# LCD_Dev_SCH_0.net
KiCad netlist of a schematic drawn in Altium Designer
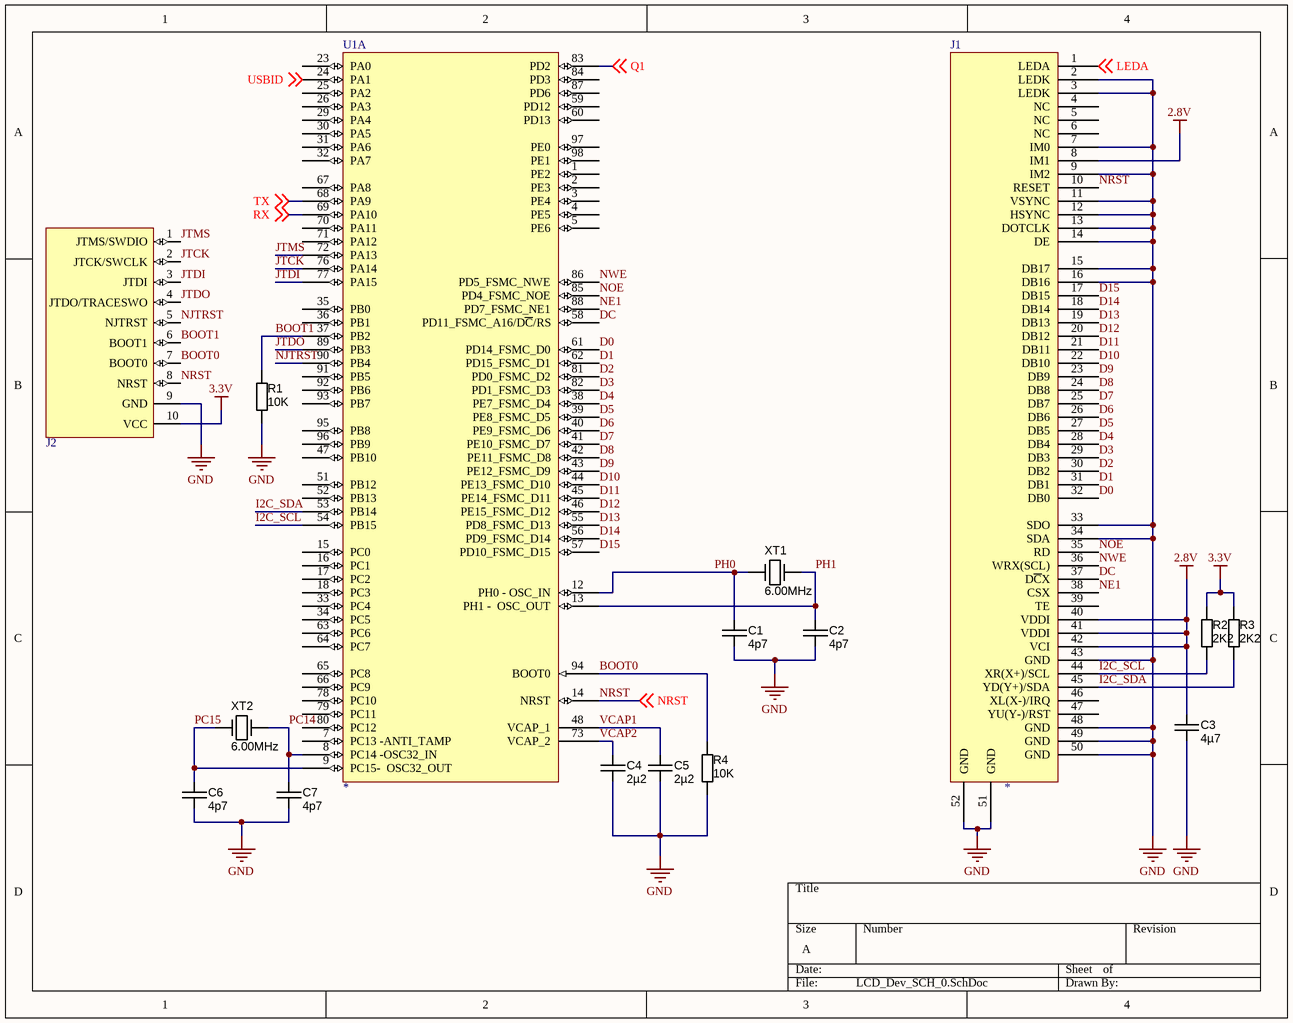
[diagram p0: LCD_Dev_SCH_0.SchDoc]

(export (version "E")
  (design (tool "Eeschema 10.0.6"))
  (components
    (comp (ref "C1")
      (value "4p7")
      (footprint "CAPC1608X90N")
      (description "Capacitor SMD Cer 4.7pF ±0.25pF 100V NP0 0603")
      (fields (field (name "TOLERANCE") "±0.25pF") (field (name "Comment") "approved sub OK"))
      (libsource (lib "PBL - Capacitors") (part "CAPC_4p7_100V_0603"))
    )
    (comp (ref "C2")
      (value "4p7")
      (footprint "CAPC1608X90N")
      (description "Capacitor SMD Cer 4.7pF ±0.25pF 100V NP0 0603")
      (fields (field (name "TOLERANCE") "±0.25pF") (field (name "Comment") "approved sub OK"))
      (libsource (lib "PBL - Capacitors") (part "CAPC_4p7_100V_0603"))
    )
    (comp (ref "C3")
      (value "4µ7")
      (footprint "CAPC2012X135N")
      (description "Capacitor SMD Cer 4.7uF 10% 16V X5R 0805")
      (fields (field (name "TOLERANCE") "±10%") (field (name "Comment") "approved sub OK"))
      (libsource (lib "PBL - Capacitors") (part "CAPC_4u7_0805"))
    )
    (comp (ref "C4")
      (value "2µ2")
      (footprint "CAPC2012X135N")
      (description "Capacitor SMD Cer 2.2uF 10% 16V X7R 0805")
      (fields (field (name "TOLERANCE") "±10%") (field (name "Comment") "approved sub OK"))
      (libsource (lib "PBL - Capacitors") (part "CAPC_2u2_0805"))
    )
    (comp (ref "C5")
      (value "2µ2")
      (footprint "CAPC2012X135N")
      (description "Capacitor SMD Cer 2.2uF 10% 16V X7R 0805")
      (fields (field (name "TOLERANCE") "±10%") (field (name "Comment") "approved sub OK"))
      (libsource (lib "PBL - Capacitors") (part "CAPC_2u2_0805"))
    )
    (comp (ref "C6")
      (value "4p7")
      (footprint "CAPC1608X90N")
      (description "Capacitor SMD Cer 4.7pF ±0.25pF 100V NP0 0603")
      (fields (field (name "TOLERANCE") "±0.25pF") (field (name "Comment") "approved sub OK"))
      (libsource (lib "PBL - Capacitors") (part "CAPC_4p7_100V_0603"))
    )
    (comp (ref "C7")
      (value "4p7")
      (footprint "CAPC1608X90N")
      (description "Capacitor SMD Cer 4.7pF ±0.25pF 100V NP0 0603")
      (fields (field (name "TOLERANCE") "±0.25pF") (field (name "Comment") "approved sub OK"))
      (libsource (lib "PBL - Capacitors") (part "CAPC_4p7_100V_0603"))
    )
    (comp (ref "J1")
      (value "*")
      (footprint "ER-CON50HT-1")
      (description "3.5”TFT LCD Display Port (i80/6800/FSMC etc)")
      (libsource (lib "co2_meter_integrated_library") (part "LCD-Port"))
    )
    (comp (ref "J2")
      (value "*")
      (footprint "SWJ-DP connector")
      (description "10 pin Serial Wire JTAG Debug Port")
      (libsource (lib "co2_meter_integrated_library") (part "SWJ-Debug Port"))
    )
    (comp (ref "R1")
      (value "10K")
      (footprint "RESC1608X55N")
      (description "Resistor SMD chip 10k Ohm 0.1W 5% 0603")
      (fields (field (name "TOLERANCE") "±5%") (field (name "Comment") "Thick Film"))
      (libsource (lib "PBL - Resistors") (part "RES_10K_0603_5%"))
    )
    (comp (ref "R2")
      (value "2K2")
      (footprint "RESC1608X55N")
      (description "Resistor SMD chip 2.2k Ohm 0.1W 5% 0603")
      (fields (field (name "TOLERANCE") "±5%") (field (name "Comment") "Thick Film"))
      (libsource (lib "PBL - Resistors") (part "RES_2K2_0603_5%"))
    )
    (comp (ref "R3")
      (value "2K2")
      (footprint "RESC1608X55N")
      (description "Resistor SMD chip 2.2k Ohm 0.1W 5% 0603")
      (fields (field (name "TOLERANCE") "±5%") (field (name "Comment") "Thick Film"))
      (libsource (lib "PBL - Resistors") (part "RES_2K2_0603_5%"))
    )
    (comp (ref "R4")
      (value "10K")
      (footprint "RESC1608X55N")
      (description "Resistor SMD chip 10k Ohm 0.1W 5% 0603")
      (fields (field (name "TOLERANCE") "±5%") (field (name "Comment") "Thick Film"))
      (libsource (lib "PBL - Resistors") (part "RES_10K_0603_5%"))
    )
    (comp (ref "U1")
      (value "*")
      (footprint "LQFP100_STM32F4")
      (description "STM32F413VHT symbol for FSMC application with designated FSMC relevant pins")
      (libsource (lib "co2_meter_integrated_library") (part "STM32F413xH"))
    )
    (comp (ref "XT1")
      (value "6.00MHz")
      (footprint "CRYSTAL_HC49-US-SM")
      (description "Resonator Ceramic 6.00 MHz 30ppm")
      (libsource (lib "PBL - Resonators") (part "Crystal_6MHz_HC49/US"))
    )
    (comp (ref "XT2")
      (value "6.00MHz")
      (footprint "CRYSTAL_HC49-US-SM")
      (description "Resonator Ceramic 6.00 MHz 30ppm")
      (libsource (lib "PBL - Resonators") (part "Crystal_6MHz_HC49/US"))
    )
  )
  (nets
    (net (code "1") (name "/BOOT0") (class "Default")
      (node (ref "J2") (pin "7") (pinfunction "BOOT0_7") (pintype "bidirectional"))
      (node (ref "R4") (pin "1") (pinfunction "1_1") (pintype "passive"))
      (node (ref "U1") (pin "94") (pinfunction "BOOT0_94") (pintype "input"))
    )
    (net (code "2") (name "/BOOT1") (class "Default")
      (node (ref "J2") (pin "6") (pinfunction "BOOT1_6") (pintype "bidirectional"))
      (node (ref "R1") (pin "1") (pinfunction "1_1") (pintype "passive"))
      (node (ref "U1") (pin "37") (pinfunction "PB2_37") (pintype "bidirectional"))
    )
    (net (code "3") (name "/D0") (class "Default")
      (node (ref "J1") (pin "32") (pinfunction "DB0_32") (pintype "passive"))
      (node (ref "U1") (pin "61") (pinfunction "PD14_FSMC_D0_61") (pintype "bidirectional"))
    )
    (net (code "4") (name "/D1") (class "Default")
      (node (ref "J1") (pin "31") (pinfunction "DB1_31") (pintype "passive"))
      (node (ref "U1") (pin "62") (pinfunction "PD15_FSMC_D1_62") (pintype "bidirectional"))
    )
    (net (code "5") (name "/D2") (class "Default")
      (node (ref "J1") (pin "30") (pinfunction "DB2_30") (pintype "passive"))
      (node (ref "U1") (pin "81") (pinfunction "PD0_FSMC_D2_81") (pintype "bidirectional"))
    )
    (net (code "6") (name "/D3") (class "Default")
      (node (ref "J1") (pin "29") (pinfunction "DB3_29") (pintype "passive"))
      (node (ref "U1") (pin "82") (pinfunction "PD1_FSMC_D3_82") (pintype "bidirectional"))
    )
    (net (code "7") (name "/D4") (class "Default")
      (node (ref "J1") (pin "28") (pinfunction "DB4_28") (pintype "passive"))
      (node (ref "U1") (pin "38") (pinfunction "PE7_FSMC_D4_38") (pintype "bidirectional"))
    )
    (net (code "8") (name "/D5") (class "Default")
      (node (ref "J1") (pin "27") (pinfunction "DB5_27") (pintype "passive"))
      (node (ref "U1") (pin "39") (pinfunction "PE8_FSMC_D5_39") (pintype "bidirectional"))
    )
    (net (code "9") (name "/D6") (class "Default")
      (node (ref "J1") (pin "26") (pinfunction "DB6_26") (pintype "passive"))
      (node (ref "U1") (pin "40") (pinfunction "PE9_FSMC_D6_40") (pintype "bidirectional"))
    )
    (net (code "10") (name "/D7") (class "Default")
      (node (ref "J1") (pin "25") (pinfunction "DB7_25") (pintype "passive"))
      (node (ref "U1") (pin "41") (pinfunction "PE10_FSMC_D7_41") (pintype "bidirectional"))
    )
    (net (code "11") (name "/D8") (class "Default")
      (node (ref "J1") (pin "24") (pinfunction "DB8_24") (pintype "passive"))
      (node (ref "U1") (pin "42") (pinfunction "PE11_FSMC_D8_42") (pintype "bidirectional"))
    )
    (net (code "12") (name "/D9") (class "Default")
      (node (ref "J1") (pin "23") (pinfunction "DB9_23") (pintype "passive"))
      (node (ref "U1") (pin "43") (pinfunction "PE12_FSMC_D9_43") (pintype "bidirectional"))
    )
    (net (code "13") (name "/D10") (class "Default")
      (node (ref "J1") (pin "22") (pinfunction "DB10_22") (pintype "passive"))
      (node (ref "U1") (pin "44") (pinfunction "PE13_FSMC_D10_44") (pintype "bidirectional"))
    )
    (net (code "14") (name "/D11") (class "Default")
      (node (ref "J1") (pin "21") (pinfunction "DB11_21") (pintype "passive"))
      (node (ref "U1") (pin "45") (pinfunction "PE14_FSMC_D11_45") (pintype "bidirectional"))
    )
    (net (code "15") (name "/D12") (class "Default")
      (node (ref "J1") (pin "20") (pinfunction "DB12_20") (pintype "passive"))
      (node (ref "U1") (pin "46") (pinfunction "PE15_FSMC_D12_46") (pintype "bidirectional"))
    )
    (net (code "16") (name "/D13") (class "Default")
      (node (ref "J1") (pin "19") (pinfunction "DB13_19") (pintype "passive"))
      (node (ref "U1") (pin "55") (pinfunction "PD8_FSMC_D13_55") (pintype "bidirectional"))
    )
    (net (code "17") (name "/D14") (class "Default")
      (node (ref "J1") (pin "18") (pinfunction "DB14_18") (pintype "passive"))
      (node (ref "U1") (pin "56") (pinfunction "PD9_FSMC_D14_56") (pintype "bidirectional"))
    )
    (net (code "18") (name "/D15") (class "Default")
      (node (ref "J1") (pin "17") (pinfunction "DB15_17") (pintype "passive"))
      (node (ref "U1") (pin "57") (pinfunction "PD10_FSMC_D15_57") (pintype "bidirectional"))
    )
    (net (code "19") (name "/DC") (class "Default")
      (node (ref "J1") (pin "37") (pinfunction "D~{C}X_37") (pintype "passive"))
      (node (ref "U1") (pin "58") (pinfunction "PD11_FSMC_A16/D~{C}/RS_58") (pintype "bidirectional"))
    )
    (net (code "20") (name "/I2C_SCL") (class "Default")
      (node (ref "J1") (pin "44") (pinfunction "XR(X+)/SCL_44") (pintype "passive"))
      (node (ref "R2") (pin "2") (pinfunction "2_2") (pintype "passive"))
      (node (ref "U1") (pin "54") (pinfunction "PB15_54") (pintype "bidirectional"))
    )
    (net (code "21") (name "/I2C_SDA") (class "Default")
      (node (ref "J1") (pin "45") (pinfunction "YD(Y+)/SDA_45") (pintype "passive"))
      (node (ref "R3") (pin "2") (pinfunction "2_2") (pintype "passive"))
      (node (ref "U1") (pin "53") (pinfunction "PB14_53") (pintype "bidirectional"))
    )
    (net (code "22") (name "/JTCK") (class "Default")
      (node (ref "J2") (pin "2") (pinfunction "JTCK/SWCLK_2") (pintype "bidirectional"))
      (node (ref "U1") (pin "76") (pinfunction "PA14_76") (pintype "bidirectional"))
    )
    (net (code "23") (name "/JTDI") (class "Default")
      (node (ref "J2") (pin "3") (pinfunction "JTDI_3") (pintype "bidirectional"))
      (node (ref "U1") (pin "77") (pinfunction "PA15_77") (pintype "bidirectional"))
    )
    (net (code "24") (name "/JTDO") (class "Default")
      (node (ref "J2") (pin "4") (pinfunction "JTDO/TRACESWO_4") (pintype "bidirectional"))
      (node (ref "U1") (pin "89") (pinfunction "PB3_89") (pintype "bidirectional"))
    )
    (net (code "25") (name "/JTMS") (class "Default")
      (node (ref "J2") (pin "1") (pinfunction "JTMS/SWDIO_1") (pintype "bidirectional"))
      (node (ref "U1") (pin "72") (pinfunction "PA13_72") (pintype "bidirectional"))
    )
    (net (code "26") (name "/NE1") (class "Default")
      (node (ref "J1") (pin "38") (pinfunction "CSX_38") (pintype "passive"))
      (node (ref "U1") (pin "88") (pinfunction "PD7_FSMC_NE1_88") (pintype "bidirectional"))
    )
    (net (code "27") (name "/NJTRST") (class "Default")
      (node (ref "J2") (pin "5") (pinfunction "NJTRST_5") (pintype "bidirectional"))
      (node (ref "U1") (pin "90") (pinfunction "PB4_90") (pintype "bidirectional"))
    )
    (net (code "28") (name "/NOE") (class "Default")
      (node (ref "J1") (pin "35") (pinfunction "RD_35") (pintype "passive"))
      (node (ref "U1") (pin "85") (pinfunction "PD4_FSMC_NOE_85") (pintype "bidirectional"))
    )
    (net (code "29") (name "/NWE") (class "Default")
      (node (ref "J1") (pin "36") (pinfunction "WRX(SCL)_36") (pintype "passive"))
      (node (ref "U1") (pin "86") (pinfunction "PD5_FSMC_NWE_86") (pintype "bidirectional"))
    )
    (net (code "30") (name "/PC14") (class "Default")
      (node (ref "C7") (pin "1") (pintype "passive"))
      (node (ref "U1") (pin "8") (pinfunction "PC14_-OSC32_IN_8") (pintype "bidirectional"))
      (node (ref "XT2") (pin "2") (pinfunction "OUT_2") (pintype "passive"))
    )
    (net (code "31") (name "/PC15") (class "Default")
      (node (ref "C6") (pin "1") (pintype "passive"))
      (node (ref "U1") (pin "9") (pinfunction "PC15-__OSC32_OUT_9") (pintype "bidirectional"))
      (node (ref "XT2") (pin "1") (pinfunction "IN_1") (pintype "passive"))
    )
    (net (code "32") (name "/PH0") (class "Default")
      (node (ref "C1") (pin "1") (pintype "passive"))
      (node (ref "U1") (pin "12") (pinfunction "PH0_-_OSC_IN_12") (pintype "bidirectional"))
      (node (ref "XT1") (pin "1") (pinfunction "IN_1") (pintype "passive"))
    )
    (net (code "33") (name "/PH1") (class "Default")
      (node (ref "C2") (pin "1") (pintype "passive"))
      (node (ref "U1") (pin "13") (pinfunction "PH1_-__OSC_OUT_13") (pintype "bidirectional"))
      (node (ref "XT1") (pin "2") (pinfunction "OUT_2") (pintype "passive"))
    )
    (net (code "34") (name "/VCAP1") (class "Default")
      (node (ref "C5") (pin "1") (pintype "passive"))
      (node (ref "U1") (pin "48") (pinfunction "VCAP_1_48") (pintype "power_in"))
    )
    (net (code "35") (name "/VCAP2") (class "Default")
      (node (ref "C4") (pin "1") (pintype "passive"))
      (node (ref "U1") (pin "73") (pinfunction "VCAP_2_73") (pintype "power_in"))
    )
    (net (code "36") (name "2.8V") (class "Default")
      (node (ref "C3") (pin "1") (pintype "passive"))
      (node (ref "J1") (pin "40") (pinfunction "VDDI_40") (pintype "passive"))
      (node (ref "J1") (pin "41") (pinfunction "VDDI_41") (pintype "passive"))
      (node (ref "J1") (pin "42") (pinfunction "VCI_42") (pintype "passive"))
      (node (ref "J1") (pin "8") (pinfunction "IM1_8") (pintype "passive"))
    )
    (net (code "37") (name "3.3V") (class "Default")
      (node (ref "J2") (pin "10") (pinfunction "VCC_10") (pintype "power_in"))
      (node (ref "R2") (pin "1") (pinfunction "1_1") (pintype "passive"))
      (node (ref "R3") (pin "1") (pinfunction "1_1") (pintype "passive"))
    )
    (net (code "38") (name "GND") (class "Default")
      (node (ref "C1") (pin "2") (pintype "passive"))
      (node (ref "C2") (pin "2") (pintype "passive"))
      (node (ref "C3") (pin "2") (pintype "passive"))
      (node (ref "C4") (pin "2") (pintype "passive"))
      (node (ref "C5") (pin "2") (pintype "passive"))
      (node (ref "C6") (pin "2") (pintype "passive"))
      (node (ref "C7") (pin "2") (pintype "passive"))
      (node (ref "J1") (pin "11") (pinfunction "VSYNC_11") (pintype "passive"))
      (node (ref "J1") (pin "12") (pinfunction "HSYNC_12") (pintype "passive"))
      (node (ref "J1") (pin "13") (pinfunction "DOTCLK_13") (pintype "passive"))
      (node (ref "J1") (pin "14") (pinfunction "DE_14") (pintype "passive"))
      (node (ref "J1") (pin "15") (pinfunction "DB17_15") (pintype "passive"))
      (node (ref "J1") (pin "16") (pinfunction "DB16_16") (pintype "passive"))
      (node (ref "J1") (pin "2") (pinfunction "LEDK_2") (pintype "power_in"))
      (node (ref "J1") (pin "3") (pinfunction "LEDK_3") (pintype "power_in"))
      (node (ref "J1") (pin "33") (pinfunction "SDO_33") (pintype "passive"))
      (node (ref "J1") (pin "34") (pinfunction "SDA_34") (pintype "passive"))
      (node (ref "J1") (pin "43") (pinfunction "GND_43") (pintype "power_in"))
      (node (ref "J1") (pin "48") (pinfunction "GND_48") (pintype "power_in"))
      (node (ref "J1") (pin "49") (pinfunction "GND_49") (pintype "power_in"))
      (node (ref "J1") (pin "50") (pinfunction "GND_50") (pintype "power_in"))
      (node (ref "J1") (pin "51") (pinfunction "GND_51") (pintype "power_in"))
      (node (ref "J1") (pin "52") (pinfunction "GND_52") (pintype "power_in"))
      (node (ref "J1") (pin "7") (pinfunction "IM0_7") (pintype "passive"))
      (node (ref "J1") (pin "9") (pinfunction "IM2_9") (pintype "passive"))
      (node (ref "J2") (pin "9") (pinfunction "GND_9") (pintype "power_in"))
      (node (ref "R1") (pin "2") (pinfunction "2_2") (pintype "passive"))
      (node (ref "R4") (pin "2") (pinfunction "2_2") (pintype "passive"))
    )
    (net (code "39") (name "LEDA") (class "Default")
      (node (ref "J1") (pin "1") (pinfunction "LEDA_1") (pintype "power_in"))
    )
    (net (code "40") (name "NRST") (class "Default")
      (node (ref "J1") (pin "10") (pinfunction "RESET_10") (pintype "passive"))
      (node (ref "J2") (pin "8") (pinfunction "NRST_8") (pintype "bidirectional"))
      (node (ref "U1") (pin "14") (pinfunction "NRST_14") (pintype "bidirectional"))
    )
    (net (code "41") (name "Q1") (class "Default")
      (node (ref "U1") (pin "83") (pinfunction "PD2_83") (pintype "bidirectional"))
    )
    (net (code "42") (name "RX") (class "Default")
      (node (ref "U1") (pin "69") (pinfunction "PA10_69") (pintype "bidirectional"))
    )
    (net (code "43") (name "TX") (class "Default")
      (node (ref "U1") (pin "68") (pinfunction "PA9_68") (pintype "bidirectional"))
    )
    (net (code "44") (name "USBID") (class "Default")
      (node (ref "U1") (pin "24") (pinfunction "PA1_24") (pintype "bidirectional"))
    )
    (net (code "45") (name "unconnected-(J1-NC-Pad4)") (class "Default")
      (node (ref "J1") (pin "4") (pinfunction "NC_4") (pintype "passive"))
    )
    (net (code "46") (name "unconnected-(J1-NC-Pad5)") (class "Default")
      (node (ref "J1") (pin "5") (pinfunction "NC_5") (pintype "passive"))
    )
    (net (code "47") (name "unconnected-(J1-NC-Pad6)") (class "Default")
      (node (ref "J1") (pin "6") (pinfunction "NC_6") (pintype "passive"))
    )
    (net (code "48") (name "unconnected-(J1-TE-Pad39)") (class "Default")
      (node (ref "J1") (pin "39") (pinfunction "TE_39") (pintype "passive"))
    )
    (net (code "49") (name "unconnected-(J1-XL(X-){slash}IRQ-Pad46)") (class "Default")
      (node (ref "J1") (pin "46") (pinfunction "XL(X-)/IRQ_46") (pintype "passive"))
    )
    (net (code "50") (name "unconnected-(J1-YU(Y-){slash}RST-Pad47)") (class "Default")
      (node (ref "J1") (pin "47") (pinfunction "YU(Y-)/RST_47") (pintype "passive"))
    )
    (net (code "51") (name "unconnected-(U1A-PA0-Pad23)") (class "Default")
      (node (ref "U1") (pin "23") (pinfunction "PA0_23") (pintype "bidirectional"))
    )
    (net (code "52") (name "unconnected-(U1A-PA2-Pad25)") (class "Default")
      (node (ref "U1") (pin "25") (pinfunction "PA2_25") (pintype "bidirectional"))
    )
    (net (code "53") (name "unconnected-(U1A-PA3-Pad26)") (class "Default")
      (node (ref "U1") (pin "26") (pinfunction "PA3_26") (pintype "bidirectional"))
    )
    (net (code "54") (name "unconnected-(U1A-PA4-Pad29)") (class "Default")
      (node (ref "U1") (pin "29") (pinfunction "PA4_29") (pintype "bidirectional"))
    )
    (net (code "55") (name "unconnected-(U1A-PA5-Pad30)") (class "Default")
      (node (ref "U1") (pin "30") (pinfunction "PA5_30") (pintype "bidirectional"))
    )
    (net (code "56") (name "unconnected-(U1A-PA6-Pad31)") (class "Default")
      (node (ref "U1") (pin "31") (pinfunction "PA6_31") (pintype "bidirectional"))
    )
    (net (code "57") (name "unconnected-(U1A-PA7-Pad32)") (class "Default")
      (node (ref "U1") (pin "32") (pinfunction "PA7_32") (pintype "bidirectional"))
    )
    (net (code "58") (name "unconnected-(U1A-PA8-Pad67)") (class "Default")
      (node (ref "U1") (pin "67") (pinfunction "PA8_67") (pintype "bidirectional"))
    )
    (net (code "59") (name "unconnected-(U1A-PA11-Pad70)") (class "Default")
      (node (ref "U1") (pin "70") (pinfunction "PA11_70") (pintype "bidirectional"))
    )
    (net (code "60") (name "unconnected-(U1A-PA12-Pad71)") (class "Default")
      (node (ref "U1") (pin "71") (pinfunction "PA12_71") (pintype "bidirectional"))
    )
    (net (code "61") (name "unconnected-(U1A-PB0-Pad35)") (class "Default")
      (node (ref "U1") (pin "35") (pinfunction "PB0_35") (pintype "bidirectional"))
    )
    (net (code "62") (name "unconnected-(U1A-PB1-Pad36)") (class "Default")
      (node (ref "U1") (pin "36") (pinfunction "PB1_36") (pintype "bidirectional"))
    )
    (net (code "63") (name "unconnected-(U1A-PB5-Pad91)") (class "Default")
      (node (ref "U1") (pin "91") (pinfunction "PB5_91") (pintype "bidirectional"))
    )
    (net (code "64") (name "unconnected-(U1A-PB6-Pad92)") (class "Default")
      (node (ref "U1") (pin "92") (pinfunction "PB6_92") (pintype "bidirectional"))
    )
    (net (code "65") (name "unconnected-(U1A-PB7-Pad93)") (class "Default")
      (node (ref "U1") (pin "93") (pinfunction "PB7_93") (pintype "bidirectional"))
    )
    (net (code "66") (name "unconnected-(U1A-PB8-Pad95)") (class "Default")
      (node (ref "U1") (pin "95") (pinfunction "PB8_95") (pintype "bidirectional"))
    )
    (net (code "67") (name "unconnected-(U1A-PB9-Pad96)") (class "Default")
      (node (ref "U1") (pin "96") (pinfunction "PB9_96") (pintype "bidirectional"))
    )
    (net (code "68") (name "unconnected-(U1A-PB10-Pad47)") (class "Default")
      (node (ref "U1") (pin "47") (pinfunction "PB10_47") (pintype "bidirectional"))
    )
    (net (code "69") (name "unconnected-(U1A-PB12-Pad51)") (class "Default")
      (node (ref "U1") (pin "51") (pinfunction "PB12_51") (pintype "bidirectional"))
    )
    (net (code "70") (name "unconnected-(U1A-PB13-Pad52)") (class "Default")
      (node (ref "U1") (pin "52") (pinfunction "PB13_52") (pintype "bidirectional"))
    )
    (net (code "71") (name "unconnected-(U1A-PC0-Pad15)") (class "Default")
      (node (ref "U1") (pin "15") (pinfunction "PC0_15") (pintype "bidirectional"))
    )
    (net (code "72") (name "unconnected-(U1A-PC1-Pad16)") (class "Default")
      (node (ref "U1") (pin "16") (pinfunction "PC1_16") (pintype "bidirectional"))
    )
    (net (code "73") (name "unconnected-(U1A-PC2-Pad17)") (class "Default")
      (node (ref "U1") (pin "17") (pinfunction "PC2_17") (pintype "bidirectional"))
    )
    (net (code "74") (name "unconnected-(U1A-PC3-Pad18)") (class "Default")
      (node (ref "U1") (pin "18") (pinfunction "PC3_18") (pintype "bidirectional"))
    )
    (net (code "75") (name "unconnected-(U1A-PC4-Pad33)") (class "Default")
      (node (ref "U1") (pin "33") (pinfunction "PC4_33") (pintype "bidirectional"))
    )
    (net (code "76") (name "unconnected-(U1A-PC5-Pad34)") (class "Default")
      (node (ref "U1") (pin "34") (pinfunction "PC5_34") (pintype "bidirectional"))
    )
    (net (code "77") (name "unconnected-(U1A-PC6-Pad63)") (class "Default")
      (node (ref "U1") (pin "63") (pinfunction "PC6_63") (pintype "bidirectional"))
    )
    (net (code "78") (name "unconnected-(U1A-PC7-Pad64)") (class "Default")
      (node (ref "U1") (pin "64") (pinfunction "PC7_64") (pintype "bidirectional"))
    )
    (net (code "79") (name "unconnected-(U1A-PC8-Pad65)") (class "Default")
      (node (ref "U1") (pin "65") (pinfunction "PC8_65") (pintype "bidirectional"))
    )
    (net (code "80") (name "unconnected-(U1A-PC9-Pad66)") (class "Default")
      (node (ref "U1") (pin "66") (pinfunction "PC9_66") (pintype "bidirectional"))
    )
    (net (code "81") (name "unconnected-(U1A-PC10-Pad78)") (class "Default")
      (node (ref "U1") (pin "78") (pinfunction "PC10_78") (pintype "bidirectional"))
    )
    (net (code "82") (name "unconnected-(U1A-PC11-Pad79)") (class "Default")
      (node (ref "U1") (pin "79") (pinfunction "PC11_79") (pintype "bidirectional"))
    )
    (net (code "83") (name "unconnected-(U1A-PC12-Pad80)") (class "Default")
      (node (ref "U1") (pin "80") (pinfunction "PC12_80") (pintype "bidirectional"))
    )
    (net (code "84") (name "unconnected-(U1A-PC13_-ANTI_TAMP-Pad7)") (class "Default")
      (node (ref "U1") (pin "7") (pinfunction "PC13_-ANTI_TAMP_7") (pintype "bidirectional"))
    )
    (net (code "85") (name "unconnected-(U1A-PD3-Pad84)") (class "Default")
      (node (ref "U1") (pin "84") (pinfunction "PD3_84") (pintype "bidirectional"))
    )
    (net (code "86") (name "unconnected-(U1A-PD6-Pad87)") (class "Default")
      (node (ref "U1") (pin "87") (pinfunction "PD6_87") (pintype "bidirectional"))
    )
    (net (code "87") (name "unconnected-(U1A-PD12-Pad59)") (class "Default")
      (node (ref "U1") (pin "59") (pinfunction "PD12_59") (pintype "bidirectional"))
    )
    (net (code "88") (name "unconnected-(U1A-PD13-Pad60)") (class "Default")
      (node (ref "U1") (pin "60") (pinfunction "PD13_60") (pintype "bidirectional"))
    )
    (net (code "89") (name "unconnected-(U1A-PE0-Pad97)") (class "Default")
      (node (ref "U1") (pin "97") (pinfunction "PE0_97") (pintype "bidirectional"))
    )
    (net (code "90") (name "unconnected-(U1A-PE1-Pad98)") (class "Default")
      (node (ref "U1") (pin "98") (pinfunction "PE1_98") (pintype "bidirectional"))
    )
    (net (code "91") (name "unconnected-(U1A-PE2-Pad1)") (class "Default")
      (node (ref "U1") (pin "1") (pinfunction "PE2_1") (pintype "bidirectional"))
    )
    (net (code "92") (name "unconnected-(U1A-PE3-Pad2)") (class "Default")
      (node (ref "U1") (pin "2") (pinfunction "PE3_2") (pintype "bidirectional"))
    )
    (net (code "93") (name "unconnected-(U1A-PE4-Pad3)") (class "Default")
      (node (ref "U1") (pin "3") (pinfunction "PE4_3") (pintype "bidirectional"))
    )
    (net (code "94") (name "unconnected-(U1A-PE5-Pad4)") (class "Default")
      (node (ref "U1") (pin "4") (pinfunction "PE5_4") (pintype "bidirectional"))
    )
    (net (code "95") (name "unconnected-(U1A-PE6-Pad5)") (class "Default")
      (node (ref "U1") (pin "5") (pinfunction "PE6_5") (pintype "bidirectional"))
    )
  )
)
